# MatrixShieldV1.net
KiCad netlist of a schematic drawn in EAGLE
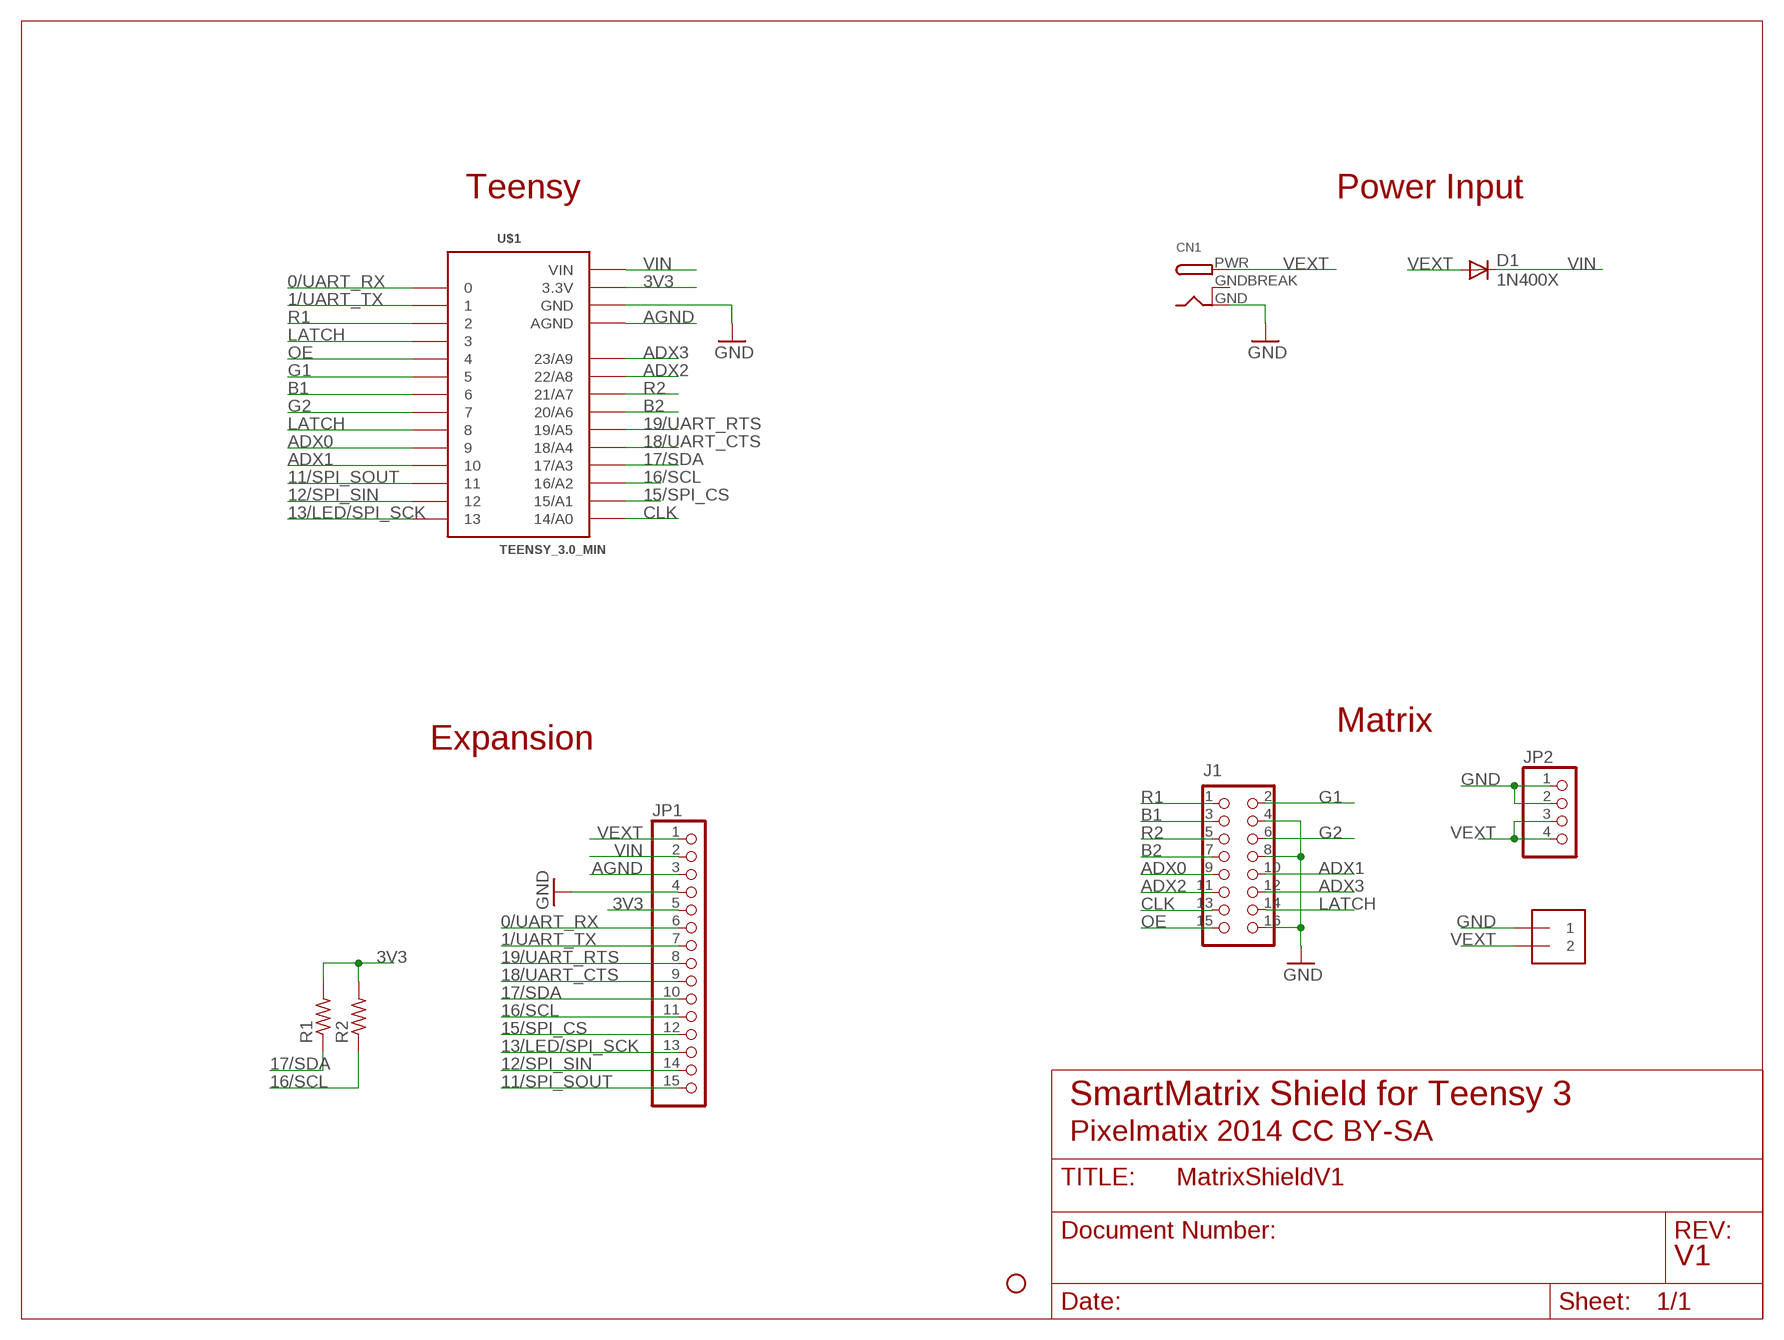
[diagram p0: schematic, sheet 1]

(export (version "E")
  (design (tool "Eeschema 10.0.6"))
  (components
    (comp (ref "CN1")
      (value "DCBARRELPTH")
      (footprint "eagle-import:DCJACK_2MM_PTH")
      (libsource (lib "eagle-import") (part "DCBARRELPTH"))
    )
    (comp (ref "D1")
      (value "1N400X")
      (footprint "eagle-import:DIODE-TH-0.3_")
      (libsource (lib "eagle-import") (part "1N400X"))
    )
    (comp (ref "J1")
      (value "CON_HEADER_2X08-PTH-SHROUDED")
      (footprint "eagle-import:PINSHRD_PTH_2X08")
      (libsource (lib "eagle-import") (part "CON_HEADER_2X08-PTH-SHROUDED"))
    )
    (comp (ref "J4")
      (value "1X2-5.0")
      (footprint "eagle-import:1X2-5.0MM")
      (libsource (lib "eagle-import") (part "1X2-5.0"))
    )
    (comp (ref "JP1")
      (value "PINHD-1X15_2.54-S")
      (footprint "eagle-import:1X15-S")
      (libsource (lib "eagle-import") (part "PINHD-1X15_2.54-S"))
    )
    (comp (ref "JP2")
      (value "PINHD-1X04_1.56")
      (footprint "eagle-import:1X04-1.56_")
      (libsource (lib "eagle-import") (part "PINHD-1X04_1.56"))
    )
    (comp (ref "JP5")
      (value "STAND-OFFSTAND-OFF-3MM")
      (footprint "eagle-import:STAND-OFF-3MM")
      (libsource (lib "eagle-import") (part "STAND-OFFSTAND-OFF-3MM"))
    )
    (comp (ref "R1")
      (value "R-US_0207/7")
      (footprint "eagle-import:0207_7")
      (libsource (lib "eagle-import") (part "R-US_0207/7"))
    )
    (comp (ref "R2")
      (value "R-US_0207/7")
      (footprint "eagle-import:0207_7")
      (libsource (lib "eagle-import") (part "R-US_0207/7"))
    )
    (comp (ref "U$1")
      (value "TEENSY_3.0_MIN")
      (footprint "eagle-import:TEENSY_3.0_MIN")
      (libsource (lib "eagle-import") (part "TEENSY_3.0_MIN"))
    )
  )
  (nets
    (net (code "1") (name "/0{slash}UART_RX") (class "Default")
      (node (ref "JP1") (pin "6") (pinfunction "6_6") (pintype "passive"))
      (node (ref "U$1") (pin "0") (pinfunction "0_0") (pintype "bidirectional"))
    )
    (net (code "2") (name "/1{slash}UART_TX") (class "Default")
      (node (ref "JP1") (pin "7") (pinfunction "7_7") (pintype "passive"))
      (node (ref "U$1") (pin "1") (pinfunction "1_1") (pintype "bidirectional"))
    )
    (net (code "3") (name "/3V3") (class "Default")
      (node (ref "JP1") (pin "5") (pinfunction "5_5") (pintype "passive"))
      (node (ref "R1") (pin "2") (pinfunction "2_2") (pintype "passive"))
      (node (ref "R2") (pin "2") (pinfunction "2_2") (pintype "passive"))
      (node (ref "U$1") (pin "3.3V") (pinfunction "3.3V_3.3V") (pintype "power_in"))
    )
    (net (code "4") (name "/11{slash}SPI_SOUT") (class "Default")
      (node (ref "JP1") (pin "15") (pinfunction "15_15") (pintype "passive"))
      (node (ref "U$1") (pin "11") (pinfunction "11_11") (pintype "bidirectional"))
    )
    (net (code "5") (name "/12{slash}SPI_SIN") (class "Default")
      (node (ref "JP1") (pin "14") (pinfunction "14_14") (pintype "passive"))
      (node (ref "U$1") (pin "12") (pinfunction "12_12") (pintype "bidirectional"))
    )
    (net (code "6") (name "/13{slash}LED{slash}SPI_SCK") (class "Default")
      (node (ref "JP1") (pin "13") (pinfunction "13_13") (pintype "passive"))
      (node (ref "U$1") (pin "13") (pinfunction "13_13") (pintype "bidirectional"))
    )
    (net (code "7") (name "/15{slash}SPI_CS") (class "Default")
      (node (ref "JP1") (pin "12") (pinfunction "12_12") (pintype "passive"))
      (node (ref "U$1") (pin "15/A1") (pinfunction "15/A1_15/A1") (pintype "bidirectional"))
    )
    (net (code "8") (name "/16{slash}SCL") (class "Default")
      (node (ref "JP1") (pin "11") (pinfunction "11_11") (pintype "passive"))
      (node (ref "R2") (pin "1") (pinfunction "1_1") (pintype "passive"))
      (node (ref "U$1") (pin "16/A2") (pinfunction "16/A2_16/A2") (pintype "bidirectional"))
    )
    (net (code "9") (name "/17{slash}SDA") (class "Default")
      (node (ref "JP1") (pin "10") (pinfunction "10_10") (pintype "passive"))
      (node (ref "R1") (pin "1") (pinfunction "1_1") (pintype "passive"))
      (node (ref "U$1") (pin "17/A3") (pinfunction "17/A3_17/A3") (pintype "bidirectional"))
    )
    (net (code "10") (name "/18{slash}UART_CTS") (class "Default")
      (node (ref "JP1") (pin "9") (pinfunction "9_9") (pintype "passive"))
      (node (ref "U$1") (pin "18/A4") (pinfunction "18/A4_18/A4") (pintype "bidirectional"))
    )
    (net (code "11") (name "/19{slash}UART_RTS") (class "Default")
      (node (ref "JP1") (pin "8") (pinfunction "8_8") (pintype "passive"))
      (node (ref "U$1") (pin "19/A5") (pinfunction "19/A5_19/A5") (pintype "bidirectional"))
    )
    (net (code "12") (name "/ADX0") (class "Default")
      (node (ref "J1") (pin "9") (pinfunction "9_9") (pintype "passive"))
      (node (ref "U$1") (pin "9") (pinfunction "9_9") (pintype "bidirectional"))
    )
    (net (code "13") (name "/ADX1") (class "Default")
      (node (ref "J1") (pin "10") (pinfunction "10_10") (pintype "passive"))
      (node (ref "U$1") (pin "10") (pinfunction "10_10") (pintype "bidirectional"))
    )
    (net (code "14") (name "/ADX2") (class "Default")
      (node (ref "J1") (pin "11") (pinfunction "11_11") (pintype "passive"))
      (node (ref "U$1") (pin "22/A8") (pinfunction "22/A8_22/A8") (pintype "bidirectional"))
    )
    (net (code "15") (name "/ADX3") (class "Default")
      (node (ref "J1") (pin "12") (pinfunction "12_12") (pintype "passive"))
      (node (ref "U$1") (pin "23/A9") (pinfunction "23/A9_23/A9") (pintype "bidirectional"))
    )
    (net (code "16") (name "/AGND") (class "Default")
      (node (ref "JP1") (pin "3") (pinfunction "3_3") (pintype "passive"))
      (node (ref "U$1") (pin "AGND") (pinfunction "AGND_AGND") (pintype "power_in"))
    )
    (net (code "17") (name "/B1") (class "Default")
      (node (ref "J1") (pin "3") (pinfunction "3_3") (pintype "passive"))
      (node (ref "U$1") (pin "6") (pinfunction "6_6") (pintype "bidirectional"))
    )
    (net (code "18") (name "/B2") (class "Default")
      (node (ref "J1") (pin "7") (pinfunction "7_7") (pintype "passive"))
      (node (ref "U$1") (pin "20/A6") (pinfunction "20/A6_20/A6") (pintype "bidirectional"))
    )
    (net (code "19") (name "/CLK") (class "Default")
      (node (ref "J1") (pin "13") (pinfunction "13_13") (pintype "passive"))
      (node (ref "U$1") (pin "14/A0") (pinfunction "14/A0_14/A0") (pintype "bidirectional"))
    )
    (net (code "20") (name "/G1") (class "Default")
      (node (ref "J1") (pin "2") (pinfunction "2_2") (pintype "passive"))
      (node (ref "U$1") (pin "5") (pinfunction "5_5") (pintype "bidirectional"))
    )
    (net (code "21") (name "/G2") (class "Default")
      (node (ref "J1") (pin "6") (pinfunction "6_6") (pintype "passive"))
      (node (ref "U$1") (pin "7") (pinfunction "7_7") (pintype "bidirectional"))
    )
    (net (code "22") (name "/GNDBREAK") (class "Default")
      (node (ref "CN1") (pin "GNDBREAK") (pinfunction "GNDBREAK_GNDBREAK") (pintype "power_in"))
    )
    (net (code "23") (name "/LATCH") (class "Default")
      (node (ref "J1") (pin "14") (pinfunction "14_14") (pintype "passive"))
      (node (ref "U$1") (pin "3") (pinfunction "3_3") (pintype "bidirectional"))
      (node (ref "U$1") (pin "8") (pinfunction "8_8") (pintype "bidirectional"))
    )
    (net (code "24") (name "/OE") (class "Default")
      (node (ref "J1") (pin "15") (pinfunction "15_15") (pintype "passive"))
      (node (ref "U$1") (pin "4") (pinfunction "4_4") (pintype "bidirectional"))
    )
    (net (code "25") (name "/R1") (class "Default")
      (node (ref "J1") (pin "1") (pinfunction "1_1") (pintype "passive"))
      (node (ref "U$1") (pin "2") (pinfunction "2_2") (pintype "bidirectional"))
    )
    (net (code "26") (name "/R2") (class "Default")
      (node (ref "J1") (pin "5") (pinfunction "5_5") (pintype "passive"))
      (node (ref "U$1") (pin "21/A7") (pinfunction "21/A7_21/A7") (pintype "bidirectional"))
    )
    (net (code "27") (name "/VEXT") (class "Default")
      (node (ref "CN1") (pin "PWR") (pinfunction "PWR_PWR") (pintype "power_in"))
      (node (ref "D1") (pin "A") (pinfunction "A_A") (pintype "passive"))
      (node (ref "J4") (pin "2") (pinfunction "2_2") (pintype "passive"))
      (node (ref "JP1") (pin "1") (pinfunction "1_1") (pintype "passive"))
      (node (ref "JP2") (pin "3") (pinfunction "3_3") (pintype "passive"))
      (node (ref "JP2") (pin "4") (pinfunction "4_4") (pintype "passive"))
    )
    (net (code "28") (name "/VIN") (class "Default")
      (node (ref "D1") (pin "C") (pinfunction "C_C") (pintype "passive"))
      (node (ref "JP1") (pin "2") (pinfunction "2_2") (pintype "passive"))
      (node (ref "U$1") (pin "VIN") (pinfunction "VIN_VIN") (pintype "power_in"))
    )
    (net (code "29") (name "GND") (class "Default")
      (node (ref "CN1") (pin "GND") (pinfunction "GND_GND") (pintype "power_in"))
      (node (ref "J1") (pin "16") (pinfunction "16_16") (pintype "passive"))
      (node (ref "J1") (pin "4") (pinfunction "4_4") (pintype "passive"))
      (node (ref "J1") (pin "8") (pinfunction "8_8") (pintype "passive"))
      (node (ref "J4") (pin "1") (pinfunction "1_1") (pintype "passive"))
      (node (ref "JP1") (pin "4") (pinfunction "4_4") (pintype "passive"))
      (node (ref "JP2") (pin "1") (pinfunction "1_1") (pintype "passive"))
      (node (ref "JP2") (pin "2") (pinfunction "2_2") (pintype "passive"))
      (node (ref "U$1") (pin "GND") (pinfunction "GND_GND") (pintype "power_in"))
    )
  )
)
